# SHDN-S11-V00-7SegmentDisplay.net
KiCad netlist of a schematic drawn in Altium Designer
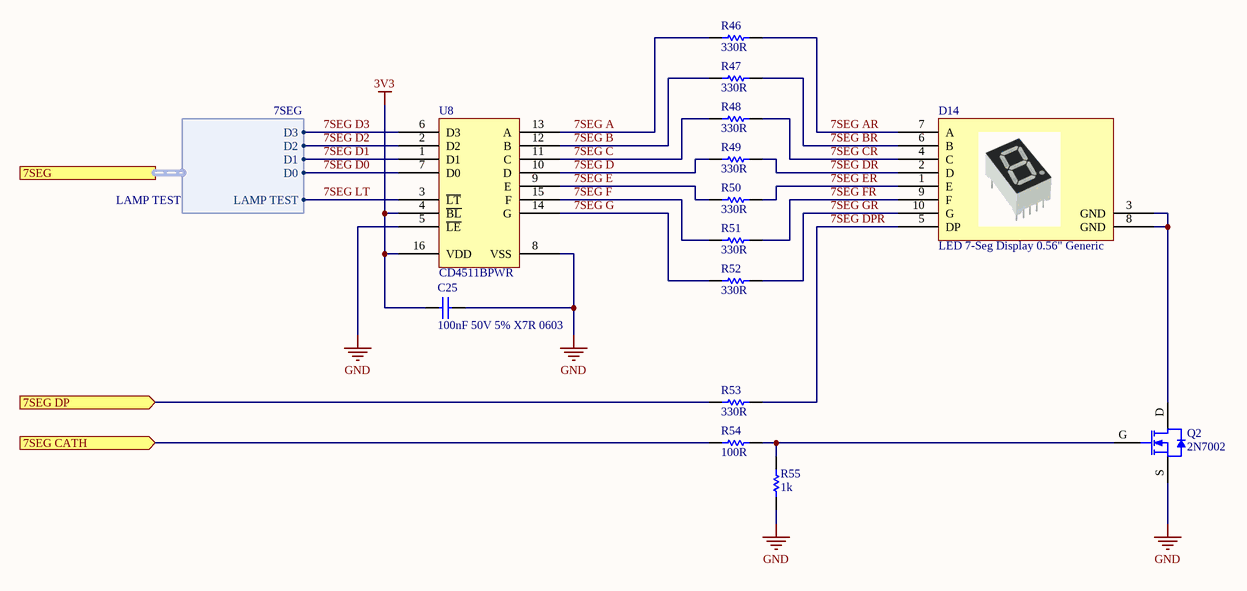
[diagram p0: SHDN-S11-V00-7SegmentDisplay.SchDoc]

(export (version "E")
  (design (tool "Eeschema 10.0.6"))
  (components
    (comp (ref "C25")
      (value "100nF 50V 5% X7R 0603")
      (footprint "Cap_Ceramic_0603")
      (description "Capacitor, Ceramic, SMD, 100nF, 50V, 5%, X7R, 0603")
      (libsource (lib "StandardCapacitors") (part "100nF 50V 5% X7R 0603"))
    )
    (comp (ref "D14")
      (value "LED 7-Seg Display 0.56\" Generic")
      (footprint "LED 7 SEG 0.56\"")
      (libsource (lib "QUTMS_LEDLibrary") (part "LED 7-Seg Display 0.56{dblquote}"))
    )
    (comp (ref "Q2")
      (value "2N7002")
      (footprint "SOT23-3")
      (libsource (lib "QUTMS_MOSFETLibrary") (part "2N7002"))
    )
    (comp (ref "R46")
      (value "330R")
      (footprint "Res_ThinFilm_0603")
      (description "Resistor, SMD, 330R, 0.1W, 5%, 0603")
      (libsource (lib "StandardResistors") (part "330R 5% 0603"))
    )
    (comp (ref "R47")
      (value "330R")
      (footprint "Res_ThinFilm_0603")
      (description "Resistor, SMD, 330R, 0.1W, 5%, 0603")
      (libsource (lib "StandardResistors") (part "330R 5% 0603"))
    )
    (comp (ref "R48")
      (value "330R")
      (footprint "Res_ThinFilm_0603")
      (description "Resistor, SMD, 330R, 0.1W, 5%, 0603")
      (libsource (lib "StandardResistors") (part "330R 5% 0603"))
    )
    (comp (ref "R49")
      (value "330R")
      (footprint "Res_ThinFilm_0603")
      (description "Resistor, SMD, 330R, 0.1W, 5%, 0603")
      (libsource (lib "StandardResistors") (part "330R 5% 0603"))
    )
    (comp (ref "R50")
      (value "330R")
      (footprint "Res_ThinFilm_0603")
      (description "Resistor, SMD, 330R, 0.1W, 5%, 0603")
      (libsource (lib "StandardResistors") (part "330R 5% 0603"))
    )
    (comp (ref "R51")
      (value "330R")
      (footprint "Res_ThinFilm_0603")
      (description "Resistor, SMD, 330R, 0.1W, 5%, 0603")
      (libsource (lib "StandardResistors") (part "330R 5% 0603"))
    )
    (comp (ref "R52")
      (value "330R")
      (footprint "Res_ThinFilm_0603")
      (description "Resistor, SMD, 330R, 0.1W, 5%, 0603")
      (libsource (lib "StandardResistors") (part "330R 5% 0603"))
    )
    (comp (ref "R53")
      (value "330R")
      (footprint "Res_ThinFilm_0603")
      (description "Resistor, SMD, 330R, 0.1W, 5%, 0603")
      (libsource (lib "StandardResistors") (part "330R 5% 0603"))
    )
    (comp (ref "R54")
      (value "100R")
      (footprint "Res_ThinFilm_0603")
      (description "Resistor, SMD, 100R, 0.1W, 5%, 0603")
      (libsource (lib "StandardResistors") (part "100R 5%, 0603"))
    )
    (comp (ref "R55")
      (value "1k")
      (footprint "Res_ThinFilm_0603")
      (description "Resistor, SMD, 1k, 0.1W, 5%, 0603")
      (libsource (lib "StandardResistors") (part "1k 5% 0603"))
    )
    (comp (ref "U8")
      (value "CD4511BPWR")
      (footprint "16-TSSOP")
      (description "LED Driver 7 Segment 16-TSSOP")
      (libsource (lib "QUTMS_LEDLibrary") (part "CD4511BPWR"))
    )
  )
  (nets
    (net (code "2") (name "/7SEG A") (class "Default")
      (node (ref "R46") (pin "1") (pinfunction "1_1") (pintype "passive"))
      (node (ref "U8") (pin "13") (pinfunction "A_13") (pintype "passive"))
    )
    (net (code "3") (name "/7SEG AR") (class "Default")
      (node (ref "D14") (pin "7") (pinfunction "A_7") (pintype "passive"))
      (node (ref "R46") (pin "2") (pinfunction "2_2") (pintype "passive"))
    )
    (net (code "4") (name "/7SEG B") (class "Default")
      (node (ref "R47") (pin "1") (pinfunction "1_1") (pintype "passive"))
      (node (ref "U8") (pin "12") (pinfunction "B_12") (pintype "passive"))
    )
    (net (code "5") (name "/7SEG BR") (class "Default")
      (node (ref "D14") (pin "6") (pinfunction "B_6") (pintype "passive"))
      (node (ref "R47") (pin "2") (pinfunction "2_2") (pintype "passive"))
    )
    (net (code "6") (name "/7SEG C") (class "Default")
      (node (ref "R48") (pin "1") (pinfunction "1_1") (pintype "passive"))
      (node (ref "U8") (pin "11") (pinfunction "C_11") (pintype "passive"))
    )
    (net (code "7") (name "/7SEG CATH") (class "Default")
      (node (ref "R54") (pin "1") (pinfunction "1_1") (pintype "passive"))
    )
    (net (code "8") (name "/7SEG CR") (class "Default")
      (node (ref "D14") (pin "4") (pinfunction "C_4") (pintype "passive"))
      (node (ref "R48") (pin "2") (pinfunction "2_2") (pintype "passive"))
    )
    (net (code "9") (name "/7SEG D") (class "Default")
      (node (ref "R49") (pin "1") (pinfunction "1_1") (pintype "passive"))
      (node (ref "U8") (pin "10") (pinfunction "D_10") (pintype "passive"))
    )
    (net (code "10") (name "/7SEG D0") (class "Default")
      (node (ref "U8") (pin "7") (pinfunction "D0_7") (pintype "passive"))
    )
    (net (code "11") (name "/7SEG D1") (class "Default")
      (node (ref "U8") (pin "1") (pinfunction "D1_1") (pintype "passive"))
    )
    (net (code "12") (name "/7SEG D2") (class "Default")
      (node (ref "U8") (pin "2") (pinfunction "D2_2") (pintype "passive"))
    )
    (net (code "13") (name "/7SEG D3") (class "Default")
      (node (ref "U8") (pin "6") (pinfunction "D3_6") (pintype "passive"))
    )
    (net (code "14") (name "/7SEG DP") (class "Default")
      (node (ref "R53") (pin "1") (pinfunction "1_1") (pintype "passive"))
    )
    (net (code "15") (name "/7SEG DPR") (class "Default")
      (node (ref "D14") (pin "5") (pinfunction "DP_5") (pintype "passive"))
      (node (ref "R53") (pin "2") (pinfunction "2_2") (pintype "passive"))
    )
    (net (code "16") (name "/7SEG DR") (class "Default")
      (node (ref "D14") (pin "2") (pinfunction "D_2") (pintype "passive"))
      (node (ref "R49") (pin "2") (pinfunction "2_2") (pintype "passive"))
    )
    (net (code "17") (name "/7SEG E") (class "Default")
      (node (ref "R50") (pin "1") (pinfunction "1_1") (pintype "passive"))
      (node (ref "U8") (pin "9") (pinfunction "E_9") (pintype "passive"))
    )
    (net (code "18") (name "/7SEG ER") (class "Default")
      (node (ref "D14") (pin "1") (pinfunction "E_1") (pintype "passive"))
      (node (ref "R50") (pin "2") (pinfunction "2_2") (pintype "passive"))
    )
    (net (code "19") (name "/7SEG F") (class "Default")
      (node (ref "R51") (pin "1") (pinfunction "1_1") (pintype "passive"))
      (node (ref "U8") (pin "15") (pinfunction "F_15") (pintype "passive"))
    )
    (net (code "20") (name "/7SEG FR") (class "Default")
      (node (ref "D14") (pin "9") (pinfunction "F_9") (pintype "passive"))
      (node (ref "R51") (pin "2") (pinfunction "2_2") (pintype "passive"))
    )
    (net (code "21") (name "/7SEG G") (class "Default")
      (node (ref "R52") (pin "1") (pinfunction "1_1") (pintype "passive"))
      (node (ref "U8") (pin "14") (pinfunction "G_14") (pintype "passive"))
    )
    (net (code "22") (name "/7SEG GR") (class "Default")
      (node (ref "D14") (pin "10") (pinfunction "G_10") (pintype "passive"))
      (node (ref "R52") (pin "2") (pinfunction "2_2") (pintype "passive"))
    )
    (net (code "23") (name "/7SEG LT") (class "Default")
      (node (ref "U8") (pin "3") (pinfunction "~{LT}_3") (pintype "passive"))
    )
    (net (code "25") (name "3V3") (class "Default")
      (node (ref "C25") (pin "1") (pinfunction "1_1") (pintype "passive"))
      (node (ref "U8") (pin "16") (pinfunction "VDD_16") (pintype "passive"))
      (node (ref "U8") (pin "4") (pinfunction "~{BL}_4") (pintype "passive"))
    )
    (net (code "26") (name "GND") (class "Default")
      (node (ref "C25") (pin "2") (pinfunction "2_2") (pintype "passive"))
      (node (ref "Q2") (pin "S") (pinfunction "S_S") (pintype "passive"))
      (node (ref "R55") (pin "1") (pinfunction "1_1") (pintype "passive"))
      (node (ref "U8") (pin "5") (pinfunction "~{LE}_5") (pintype "passive"))
      (node (ref "U8") (pin "8") (pinfunction "VSS_8") (pintype "passive"))
    )
    (net (code "27") (name "Net-(D14-GND-Pad3)") (class "Default")
      (node (ref "D14") (pin "3") (pinfunction "GND_3") (pintype "passive"))
      (node (ref "D14") (pin "8") (pinfunction "GND_8") (pintype "passive"))
      (node (ref "Q2") (pin "D") (pinfunction "D_D") (pintype "passive"))
    )
    (net (code "28") (name "Net-(Q2-PadG)") (class "Default")
      (node (ref "Q2") (pin "G") (pinfunction "G_G") (pintype "passive"))
      (node (ref "R54") (pin "2") (pinfunction "2_2") (pintype "passive"))
      (node (ref "R55") (pin "2") (pinfunction "2_2") (pintype "passive"))
    )
  )
)
